# wr841n-pic.net
KiCad netlist of a schematic drawn in EAGLE
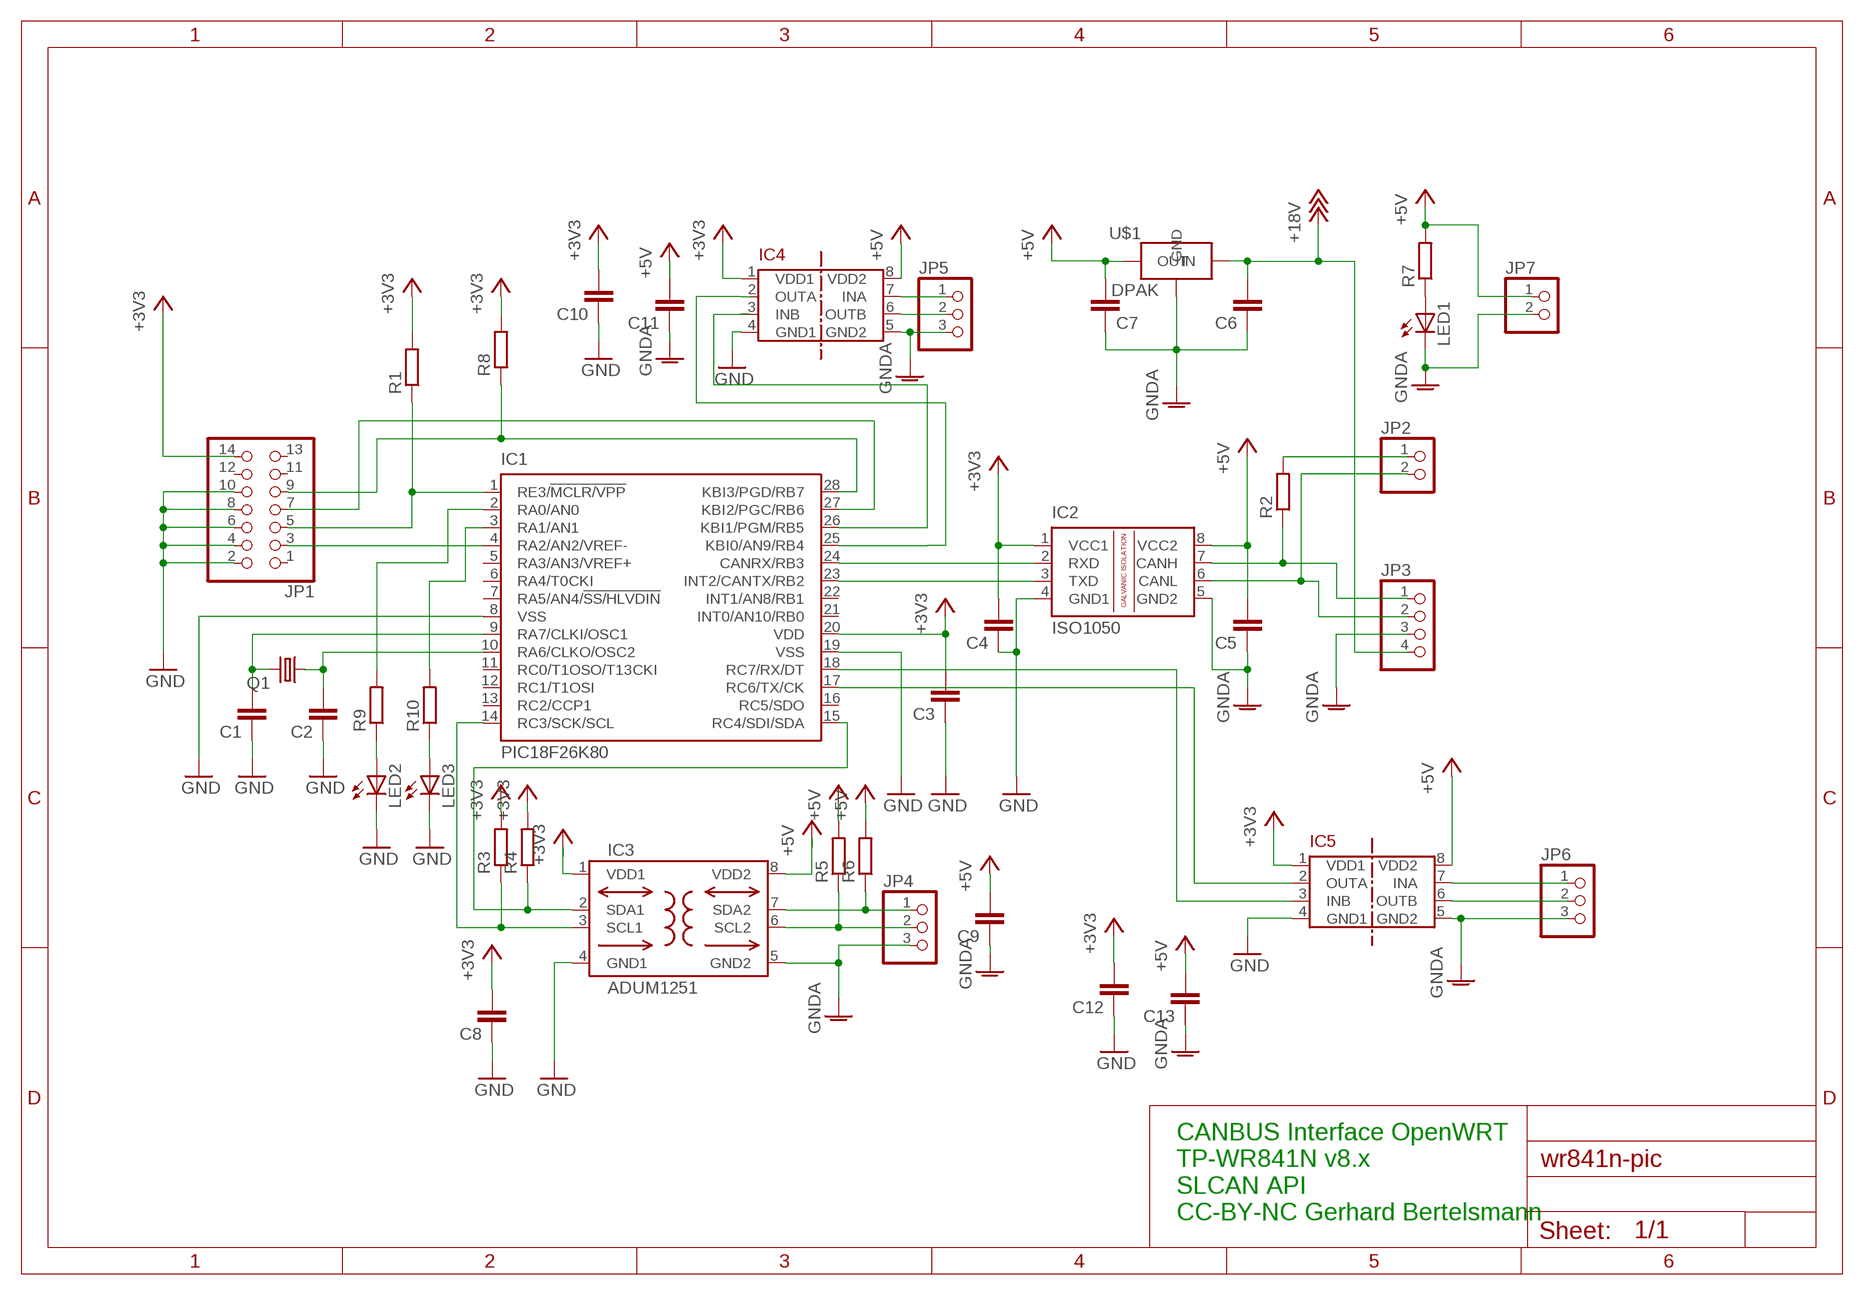
[diagram p0: schematic, sheet 1]

(export (version "E")
  (design (tool "Eeschema 10.0.6"))
  (components
    (comp (ref "C1")
      (value "C-EUC1206")
      (footprint "eagle-import:C1206")
      (libsource (lib "eagle-import") (part "C-EUC1206"))
    )
    (comp (ref "C2")
      (value "C-EUC1206")
      (footprint "eagle-import:C1206")
      (libsource (lib "eagle-import") (part "C-EUC1206"))
    )
    (comp (ref "C3")
      (value "C-EUC1206")
      (footprint "eagle-import:C1206")
      (libsource (lib "eagle-import") (part "C-EUC1206"))
    )
    (comp (ref "C4")
      (value "C-EUC1206")
      (footprint "eagle-import:C1206")
      (libsource (lib "eagle-import") (part "C-EUC1206"))
    )
    (comp (ref "C5")
      (value "C-EUC1206")
      (footprint "eagle-import:C1206")
      (libsource (lib "eagle-import") (part "C-EUC1206"))
    )
    (comp (ref "C6")
      (value "C-EUC1206")
      (footprint "eagle-import:C1206")
      (libsource (lib "eagle-import") (part "C-EUC1206"))
    )
    (comp (ref "C7")
      (value "C-EUC1206")
      (footprint "eagle-import:C1206")
      (libsource (lib "eagle-import") (part "C-EUC1206"))
    )
    (comp (ref "C8")
      (value "C-EUC1206")
      (footprint "eagle-import:C1206")
      (libsource (lib "eagle-import") (part "C-EUC1206"))
    )
    (comp (ref "C9")
      (value "C-EUC1206")
      (footprint "eagle-import:C1206")
      (libsource (lib "eagle-import") (part "C-EUC1206"))
    )
    (comp (ref "C10")
      (value "C-EUC1206")
      (footprint "eagle-import:C1206")
      (libsource (lib "eagle-import") (part "C-EUC1206"))
    )
    (comp (ref "C11")
      (value "C-EUC1206")
      (footprint "eagle-import:C1206")
      (libsource (lib "eagle-import") (part "C-EUC1206"))
    )
    (comp (ref "C12")
      (value "C-EUC1206")
      (footprint "eagle-import:C1206")
      (libsource (lib "eagle-import") (part "C-EUC1206"))
    )
    (comp (ref "C13")
      (value "C-EUC1206")
      (footprint "eagle-import:C1206")
      (libsource (lib "eagle-import") (part "C-EUC1206"))
    )
    (comp (ref "IC1")
      (value "PIC18F26K80")
      (footprint "eagle-import:SO28W")
      (libsource (lib "eagle-import") (part "PIC18F26K80-E/SO"))
    )
    (comp (ref "IC2")
      (value "ISO1050")
      (footprint "eagle-import:DUB-R-PDSO-G8")
      (fields (field (name "MPN") "ISO1050DUBR"))
      (libsource (lib "eagle-import") (part "ISO1050DUB"))
    )
    (comp (ref "IC3")
      (value "ADUM1251")
      (footprint "eagle-import:SO8-COOL")
      (libsource (lib "eagle-import") (part "ADUM1251"))
    )
    (comp (ref "IC4")
      (value "ADUM1201")
      (footprint "eagle-import:SO8")
      (libsource (lib "eagle-import") (part "ADUM1201"))
    )
    (comp (ref "IC5")
      (value "ADUM1201")
      (footprint "eagle-import:SO8")
      (libsource (lib "eagle-import") (part "ADUM1201"))
    )
    (comp (ref "JP1")
      (value "PINHD-2X7")
      (footprint "eagle-import:2X07")
      (libsource (lib "eagle-import") (part "PINHD-2X7"))
    )
    (comp (ref "JP2")
      (value "PINHD-1X2")
      (footprint "eagle-import:1X02")
      (libsource (lib "eagle-import") (part "PINHD-1X2"))
    )
    (comp (ref "JP3")
      (value "PINHD-1X4")
      (footprint "eagle-import:1X04")
      (libsource (lib "eagle-import") (part "PINHD-1X4"))
    )
    (comp (ref "JP4")
      (value "PINHD-1X3")
      (footprint "eagle-import:1X03")
      (libsource (lib "eagle-import") (part "PINHD-1X3"))
    )
    (comp (ref "JP5")
      (value "PINHD-1X3")
      (footprint "eagle-import:1X03")
      (libsource (lib "eagle-import") (part "PINHD-1X3"))
    )
    (comp (ref "JP6")
      (value "PINHD-1X3")
      (footprint "eagle-import:1X03")
      (libsource (lib "eagle-import") (part "PINHD-1X3"))
    )
    (comp (ref "JP7")
      (value "PINHD-1X2")
      (footprint "eagle-import:1X02")
      (libsource (lib "eagle-import") (part "PINHD-1X2"))
    )
    (comp (ref "LED1")
      (value "LEDCHIPLED_1206")
      (footprint "eagle-import:CHIPLED_1206")
      (libsource (lib "eagle-import") (part "LEDCHIPLED_1206"))
    )
    (comp (ref "LED2")
      (value "LEDCHIPLED_1206")
      (footprint "eagle-import:CHIPLED_1206")
      (libsource (lib "eagle-import") (part "LEDCHIPLED_1206"))
    )
    (comp (ref "LED3")
      (value "LEDCHIPLED_1206")
      (footprint "eagle-import:CHIPLED_1206")
      (libsource (lib "eagle-import") (part "LEDCHIPLED_1206"))
    )
    (comp (ref "Q1")
      (value "CRYSTALHC49UP")
      (footprint "eagle-import:HC49UP")
      (libsource (lib "eagle-import") (part "CRYSTALHC49UP"))
    )
    (comp (ref "R1")
      (value "R-EU_R1206")
      (footprint "eagle-import:R1206")
      (libsource (lib "eagle-import") (part "R-EU_R1206"))
    )
    (comp (ref "R2")
      (value "R-EU_R1206")
      (footprint "eagle-import:R1206")
      (libsource (lib "eagle-import") (part "R-EU_R1206"))
    )
    (comp (ref "R3")
      (value "R-EU_R1206")
      (footprint "eagle-import:R1206")
      (libsource (lib "eagle-import") (part "R-EU_R1206"))
    )
    (comp (ref "R4")
      (value "R-EU_R1206")
      (footprint "eagle-import:R1206")
      (libsource (lib "eagle-import") (part "R-EU_R1206"))
    )
    (comp (ref "R5")
      (value "R-EU_R1206")
      (footprint "eagle-import:R1206")
      (libsource (lib "eagle-import") (part "R-EU_R1206"))
    )
    (comp (ref "R6")
      (value "R-EU_R1206")
      (footprint "eagle-import:R1206")
      (libsource (lib "eagle-import") (part "R-EU_R1206"))
    )
    (comp (ref "R7")
      (value "R-EU_R1206")
      (footprint "eagle-import:R1206")
      (libsource (lib "eagle-import") (part "R-EU_R1206"))
    )
    (comp (ref "R8")
      (value "R-EU_R1206")
      (footprint "eagle-import:R1206")
      (libsource (lib "eagle-import") (part "R-EU_R1206"))
    )
    (comp (ref "R9")
      (value "R-EU_R1206")
      (footprint "eagle-import:R1206")
      (libsource (lib "eagle-import") (part "R-EU_R1206"))
    )
    (comp (ref "R10")
      (value "R-EU_R1206")
      (footprint "eagle-import:R1206")
      (libsource (lib "eagle-import") (part "R-EU_R1206"))
    )
    (comp (ref "U$1")
      (value "7805-DPAK")
      (footprint "eagle-import:7805-DPAK")
      (libsource (lib "eagle-import") (part "7805-DPAK"))
    )
  )
  (nets
    (net (code "1") (name "+3V3") (class "Default")
      (node (ref "C10") (pin "2") (pinfunction "2_2") (pintype "passive"))
      (node (ref "C12") (pin "2") (pinfunction "2_2") (pintype "passive"))
      (node (ref "C3") (pin "2") (pinfunction "2_2") (pintype "passive"))
      (node (ref "C4") (pin "2") (pinfunction "2_2") (pintype "passive"))
      (node (ref "C8") (pin "2") (pinfunction "2_2") (pintype "passive"))
      (node (ref "IC1") (pin "20") (pinfunction "VDD_20") (pintype "power_in"))
      (node (ref "IC2") (pin "1") (pinfunction "VCC1_1") (pintype "input"))
      (node (ref "IC3") (pin "1") (pinfunction "VDD1_1") (pintype "power_in"))
      (node (ref "IC4") (pin "1") (pinfunction "VDD1_1") (pintype "power_in"))
      (node (ref "IC5") (pin "1") (pinfunction "VDD1_1") (pintype "power_in"))
      (node (ref "JP1") (pin "14") (pinfunction "14_14") (pintype "passive"))
      (node (ref "R1") (pin "2") (pinfunction "2_2") (pintype "passive"))
      (node (ref "R3") (pin "2") (pinfunction "2_2") (pintype "passive"))
      (node (ref "R4") (pin "2") (pinfunction "2_2") (pintype "passive"))
      (node (ref "R8") (pin "2") (pinfunction "2_2") (pintype "passive"))
    )
    (net (code "2") (name "+5V") (class "Default")
      (node (ref "C11") (pin "2") (pinfunction "2_2") (pintype "passive"))
      (node (ref "C13") (pin "2") (pinfunction "2_2") (pintype "passive"))
      (node (ref "C5") (pin "2") (pinfunction "2_2") (pintype "passive"))
      (node (ref "C7") (pin "2") (pinfunction "2_2") (pintype "passive"))
      (node (ref "C9") (pin "2") (pinfunction "2_2") (pintype "passive"))
      (node (ref "IC2") (pin "8") (pinfunction "VCC2_8") (pintype "input"))
      (node (ref "IC3") (pin "8") (pinfunction "VDD2_8") (pintype "power_in"))
      (node (ref "IC4") (pin "8") (pinfunction "VDD2_8") (pintype "power_in"))
      (node (ref "IC5") (pin "8") (pinfunction "VDD2_8") (pintype "power_in"))
      (node (ref "JP7") (pin "1") (pinfunction "1_1") (pintype "passive"))
      (node (ref "R5") (pin "2") (pinfunction "2_2") (pintype "passive"))
      (node (ref "R6") (pin "2") (pinfunction "2_2") (pintype "passive"))
      (node (ref "R7") (pin "2") (pinfunction "2_2") (pintype "passive"))
      (node (ref "U$1") (pin "OUT") (pinfunction "OUT_OUT") (pintype "bidirectional"))
    )
    (net (code "3") (name "+18V") (class "Default")
      (node (ref "C6") (pin "2") (pinfunction "2_2") (pintype "passive"))
      (node (ref "JP3") (pin "4") (pinfunction "4_4") (pintype "passive"))
      (node (ref "U$1") (pin "IN") (pinfunction "IN_IN") (pintype "bidirectional"))
    )
    (net (code "4") (name "GND") (class "Default")
      (node (ref "C1") (pin "1") (pinfunction "1_1") (pintype "passive"))
      (node (ref "C10") (pin "1") (pinfunction "1_1") (pintype "passive"))
      (node (ref "C12") (pin "1") (pinfunction "1_1") (pintype "passive"))
      (node (ref "C2") (pin "1") (pinfunction "1_1") (pintype "passive"))
      (node (ref "C3") (pin "1") (pinfunction "1_1") (pintype "passive"))
      (node (ref "C4") (pin "1") (pinfunction "1_1") (pintype "passive"))
      (node (ref "C8") (pin "1") (pinfunction "1_1") (pintype "passive"))
      (node (ref "IC1") (pin "19") (pinfunction "VSS_19") (pintype "power_in"))
      (node (ref "IC1") (pin "8") (pinfunction "VSS_8") (pintype "power_in"))
      (node (ref "IC2") (pin "4") (pinfunction "GND1_4") (pintype "input"))
      (node (ref "IC3") (pin "4") (pinfunction "GND1_4") (pintype "power_in"))
      (node (ref "IC4") (pin "4") (pinfunction "GND1_4") (pintype "power_in"))
      (node (ref "IC5") (pin "4") (pinfunction "GND1_4") (pintype "power_in"))
      (node (ref "JP1") (pin "10") (pinfunction "10_10") (pintype "passive"))
      (node (ref "JP1") (pin "2") (pinfunction "2_2") (pintype "passive"))
      (node (ref "JP1") (pin "4") (pinfunction "4_4") (pintype "passive"))
      (node (ref "JP1") (pin "6") (pinfunction "6_6") (pintype "passive"))
      (node (ref "JP1") (pin "8") (pinfunction "8_8") (pintype "passive"))
      (node (ref "LED2") (pin "C") (pinfunction "C_C") (pintype "passive"))
      (node (ref "LED3") (pin "C") (pinfunction "C_C") (pintype "passive"))
    )
    (net (code "5") (name "GNDA") (class "Default")
      (node (ref "C11") (pin "1") (pinfunction "1_1") (pintype "passive"))
      (node (ref "C13") (pin "1") (pinfunction "1_1") (pintype "passive"))
      (node (ref "C5") (pin "1") (pinfunction "1_1") (pintype "passive"))
      (node (ref "C6") (pin "1") (pinfunction "1_1") (pintype "passive"))
      (node (ref "C7") (pin "1") (pinfunction "1_1") (pintype "passive"))
      (node (ref "C9") (pin "1") (pinfunction "1_1") (pintype "passive"))
      (node (ref "IC2") (pin "5") (pinfunction "GND2_5") (pintype "input"))
      (node (ref "IC3") (pin "5") (pinfunction "GND2_5") (pintype "power_in"))
      (node (ref "IC4") (pin "5") (pinfunction "GND2_5") (pintype "power_in"))
      (node (ref "IC5") (pin "5") (pinfunction "GND2_5") (pintype "power_in"))
      (node (ref "JP3") (pin "3") (pinfunction "3_3") (pintype "passive"))
      (node (ref "JP4") (pin "3") (pinfunction "3_3") (pintype "passive"))
      (node (ref "JP5") (pin "3") (pinfunction "3_3") (pintype "passive"))
      (node (ref "JP6") (pin "3") (pinfunction "3_3") (pintype "passive"))
      (node (ref "JP7") (pin "2") (pinfunction "2_2") (pintype "passive"))
      (node (ref "LED1") (pin "C") (pinfunction "C_C") (pintype "passive"))
      (node (ref "U$1") (pin "GND") (pinfunction "GND_GND") (pintype "bidirectional"))
    )
    (net (code "6") (name "Net-(IC1-CANRX{slash}RB3)") (class "Default")
      (node (ref "IC1") (pin "24") (pinfunction "CANRX/RB3_24") (pintype "bidirectional"))
      (node (ref "IC2") (pin "2") (pinfunction "RXD_2") (pintype "input"))
    )
    (net (code "7") (name "Net-(IC1-INT2{slash}CANTX{slash}RB2)") (class "Default")
      (node (ref "IC1") (pin "23") (pinfunction "INT2/CANTX/RB2_23") (pintype "bidirectional"))
      (node (ref "IC2") (pin "3") (pinfunction "TXD_3") (pintype "input"))
    )
    (net (code "8") (name "Net-(IC1-KBI0{slash}AN9{slash}RB4)") (class "Default")
      (node (ref "IC1") (pin "25") (pinfunction "KBI0/AN9/RB4_25") (pintype "bidirectional"))
      (node (ref "IC4") (pin "2") (pinfunction "OUTA_2") (pintype "output"))
    )
    (net (code "9") (name "Net-(IC1-KBI1{slash}PGM{slash}RB5)") (class "Default")
      (node (ref "IC1") (pin "26") (pinfunction "KBI1/PGM/RB5_26") (pintype "bidirectional"))
      (node (ref "IC4") (pin "3") (pinfunction "INB_3") (pintype "input"))
    )
    (net (code "10") (name "Net-(IC1-KBI2{slash}PGC{slash}RB6)") (class "Default")
      (node (ref "IC1") (pin "27") (pinfunction "KBI2/PGC/RB6_27") (pintype "bidirectional"))
      (node (ref "JP1") (pin "7") (pinfunction "7_7") (pintype "passive"))
    )
    (net (code "11") (name "Net-(IC1-KBI3{slash}PGD{slash}RB7)") (class "Default")
      (node (ref "IC1") (pin "28") (pinfunction "KBI3/PGD/RB7_28") (pintype "bidirectional"))
      (node (ref "JP1") (pin "9") (pinfunction "9_9") (pintype "passive"))
      (node (ref "R8") (pin "1") (pinfunction "1_1") (pintype "passive"))
    )
    (net (code "12") (name "Net-(IC1-RA0{slash}AN0)") (class "Default")
      (node (ref "IC1") (pin "2") (pinfunction "RA0/AN0_2") (pintype "bidirectional"))
      (node (ref "R9") (pin "2") (pinfunction "2_2") (pintype "passive"))
    )
    (net (code "13") (name "Net-(IC1-RA1{slash}AN1)") (class "Default")
      (node (ref "IC1") (pin "3") (pinfunction "RA1/AN1_3") (pintype "bidirectional"))
      (node (ref "R10") (pin "2") (pinfunction "2_2") (pintype "passive"))
    )
    (net (code "14") (name "Net-(IC1-RA2{slash}AN2{slash}VREF-)") (class "Default")
      (node (ref "IC1") (pin "4") (pinfunction "RA2/AN2/VREF-_4") (pintype "bidirectional"))
      (node (ref "JP1") (pin "3") (pinfunction "3_3") (pintype "passive"))
    )
    (net (code "15") (name "Net-(IC1-RA6{slash}CLKO{slash}OSC2)") (class "Default")
      (node (ref "C2") (pin "2") (pinfunction "2_2") (pintype "passive"))
      (node (ref "IC1") (pin "10") (pinfunction "RA6/CLKO/OSC2_10") (pintype "output"))
      (node (ref "Q1") (pin "1") (pinfunction "1_1") (pintype "passive"))
    )
    (net (code "16") (name "Net-(IC1-RA7{slash}CLKI{slash}OSC1)") (class "Default")
      (node (ref "C1") (pin "2") (pinfunction "2_2") (pintype "passive"))
      (node (ref "IC1") (pin "9") (pinfunction "RA7/CLKI/OSC1_9") (pintype "input"))
      (node (ref "Q1") (pin "2") (pinfunction "2_2") (pintype "passive"))
    )
    (net (code "17") (name "Net-(IC1-RC3{slash}SCK{slash}SCL)") (class "Default")
      (node (ref "IC1") (pin "14") (pinfunction "RC3/SCK/SCL_14") (pintype "bidirectional"))
      (node (ref "IC3") (pin "3") (pinfunction "SCL1_3") (pintype "bidirectional"))
      (node (ref "R3") (pin "1") (pinfunction "1_1") (pintype "passive"))
    )
    (net (code "18") (name "Net-(IC1-RC4{slash}SDI{slash}SDA)") (class "Default")
      (node (ref "IC1") (pin "15") (pinfunction "RC4/SDI/SDA_15") (pintype "bidirectional"))
      (node (ref "IC3") (pin "2") (pinfunction "SDA1_2") (pintype "bidirectional"))
      (node (ref "R4") (pin "1") (pinfunction "1_1") (pintype "passive"))
    )
    (net (code "19") (name "Net-(IC1-RC6{slash}TX{slash}CK)") (class "Default")
      (node (ref "IC1") (pin "17") (pinfunction "RC6/TX/CK_17") (pintype "bidirectional"))
      (node (ref "IC5") (pin "2") (pinfunction "OUTA_2") (pintype "output"))
    )
    (net (code "20") (name "Net-(IC1-RC7{slash}RX{slash}DT)") (class "Default")
      (node (ref "IC1") (pin "18") (pinfunction "RC7/RX/DT_18") (pintype "bidirectional"))
      (node (ref "IC5") (pin "3") (pinfunction "INB_3") (pintype "input"))
    )
    (net (code "21") (name "Net-(IC1-RE3{slash}~{MCLR{slash}VPP})") (class "Default")
      (node (ref "IC1") (pin "1") (pinfunction "RE3/~{MCLR/VPP}_1") (pintype "input"))
      (node (ref "JP1") (pin "5") (pinfunction "5_5") (pintype "passive"))
      (node (ref "R1") (pin "1") (pinfunction "1_1") (pintype "passive"))
    )
    (net (code "22") (name "Net-(IC2-CANH)") (class "Default")
      (node (ref "IC2") (pin "7") (pinfunction "CANH_7") (pintype "input"))
      (node (ref "JP3") (pin "1") (pinfunction "1_1") (pintype "passive"))
      (node (ref "R2") (pin "1") (pinfunction "1_1") (pintype "passive"))
    )
    (net (code "23") (name "Net-(IC2-CANL)") (class "Default")
      (node (ref "IC2") (pin "6") (pinfunction "CANL_6") (pintype "input"))
      (node (ref "JP2") (pin "2") (pinfunction "2_2") (pintype "passive"))
      (node (ref "JP3") (pin "2") (pinfunction "2_2") (pintype "passive"))
    )
    (net (code "24") (name "Net-(IC3-SCL2)") (class "Default")
      (node (ref "IC3") (pin "6") (pinfunction "SCL2_6") (pintype "bidirectional"))
      (node (ref "JP4") (pin "2") (pinfunction "2_2") (pintype "passive"))
      (node (ref "R5") (pin "1") (pinfunction "1_1") (pintype "passive"))
    )
    (net (code "25") (name "Net-(IC3-SDA2)") (class "Default")
      (node (ref "IC3") (pin "7") (pinfunction "SDA2_7") (pintype "bidirectional"))
      (node (ref "JP4") (pin "1") (pinfunction "1_1") (pintype "passive"))
      (node (ref "R6") (pin "1") (pinfunction "1_1") (pintype "passive"))
    )
    (net (code "26") (name "Net-(IC4-INA)") (class "Default")
      (node (ref "IC4") (pin "7") (pinfunction "INA_7") (pintype "input"))
      (node (ref "JP5") (pin "1") (pinfunction "1_1") (pintype "passive"))
    )
    (net (code "27") (name "Net-(IC4-OUTB)") (class "Default")
      (node (ref "IC4") (pin "6") (pinfunction "OUTB_6") (pintype "output"))
      (node (ref "JP5") (pin "2") (pinfunction "2_2") (pintype "passive"))
    )
    (net (code "28") (name "Net-(IC5-INA)") (class "Default")
      (node (ref "IC5") (pin "7") (pinfunction "INA_7") (pintype "input"))
      (node (ref "JP6") (pin "1") (pinfunction "1_1") (pintype "passive"))
    )
    (net (code "29") (name "Net-(IC5-OUTB)") (class "Default")
      (node (ref "IC5") (pin "6") (pinfunction "OUTB_6") (pintype "output"))
      (node (ref "JP6") (pin "2") (pinfunction "2_2") (pintype "passive"))
    )
    (net (code "30") (name "Net-(JP2-Pad1)") (class "Default")
      (node (ref "JP2") (pin "1") (pinfunction "1_1") (pintype "passive"))
      (node (ref "R2") (pin "2") (pinfunction "2_2") (pintype "passive"))
    )
    (net (code "31") (name "Net-(LED1-PadA)") (class "Default")
      (node (ref "LED1") (pin "A") (pinfunction "A_A") (pintype "passive"))
      (node (ref "R7") (pin "1") (pinfunction "1_1") (pintype "passive"))
    )
    (net (code "32") (name "Net-(LED2-PadA)") (class "Default")
      (node (ref "LED2") (pin "A") (pinfunction "A_A") (pintype "passive"))
      (node (ref "R9") (pin "1") (pinfunction "1_1") (pintype "passive"))
    )
    (net (code "33") (name "Net-(LED3-PadA)") (class "Default")
      (node (ref "LED3") (pin "A") (pinfunction "A_A") (pintype "passive"))
      (node (ref "R10") (pin "1") (pinfunction "1_1") (pintype "passive"))
    )
    (net (code "34") (name "unconnected-(IC1-INT0{slash}AN10{slash}RB0-Pad21)") (class "Default")
      (node (ref "IC1") (pin "21") (pinfunction "INT0/AN10/RB0_21") (pintype "bidirectional"))
    )
    (net (code "35") (name "unconnected-(IC1-INT1{slash}AN8{slash}RB1-Pad22)") (class "Default")
      (node (ref "IC1") (pin "22") (pinfunction "INT1/AN8/RB1_22") (pintype "bidirectional"))
    )
    (net (code "36") (name "unconnected-(IC1-RA3{slash}AN3{slash}VREF+-Pad5)") (class "Default")
      (node (ref "IC1") (pin "5") (pinfunction "RA3/AN3/VREF+_5") (pintype "bidirectional"))
    )
    (net (code "37") (name "unconnected-(IC1-RA4{slash}T0CKI-Pad6)") (class "Default")
      (node (ref "IC1") (pin "6") (pinfunction "RA4/T0CKI_6") (pintype "bidirectional"))
    )
    (net (code "38") (name "unconnected-(IC1-RA5{slash}AN4{slash}~{SS{slash}HLVDIN}-Pad7)") (class "Default")
      (node (ref "IC1") (pin "7") (pinfunction "RA5/AN4/~{SS/HLVDIN}_7") (pintype "bidirectional"))
    )
    (net (code "39") (name "unconnected-(IC1-RC0{slash}T1OSO{slash}T13CKI-Pad11)") (class "Default")
      (node (ref "IC1") (pin "11") (pinfunction "RC0/T1OSO/T13CKI_11") (pintype "bidirectional"))
    )
    (net (code "40") (name "unconnected-(IC1-RC1{slash}T1OSI-Pad12)") (class "Default")
      (node (ref "IC1") (pin "12") (pinfunction "RC1/T1OSI_12") (pintype "bidirectional"))
    )
    (net (code "41") (name "unconnected-(IC1-RC2{slash}CCP1-Pad13)") (class "Default")
      (node (ref "IC1") (pin "13") (pinfunction "RC2/CCP1_13") (pintype "bidirectional"))
    )
    (net (code "42") (name "unconnected-(IC1-RC5{slash}SDO-Pad16)") (class "Default")
      (node (ref "IC1") (pin "16") (pinfunction "RC5/SDO_16") (pintype "bidirectional"))
    )
    (net (code "43") (name "unconnected-(JP1-Pad1)") (class "Default")
      (node (ref "JP1") (pin "1") (pinfunction "1_1") (pintype "passive"))
    )
    (net (code "44") (name "unconnected-(JP1-Pad11)") (class "Default")
      (node (ref "JP1") (pin "11") (pinfunction "11_11") (pintype "passive"))
    )
    (net (code "45") (name "unconnected-(JP1-Pad12)") (class "Default")
      (node (ref "JP1") (pin "12") (pinfunction "12_12") (pintype "passive"))
    )
    (net (code "46") (name "unconnected-(JP1-Pad13)") (class "Default")
      (node (ref "JP1") (pin "13") (pinfunction "13_13") (pintype "passive"))
    )
  )
)
